# nrf52_pcb_layout.net
KiCad netlist of a schematic drawn in EAGLE
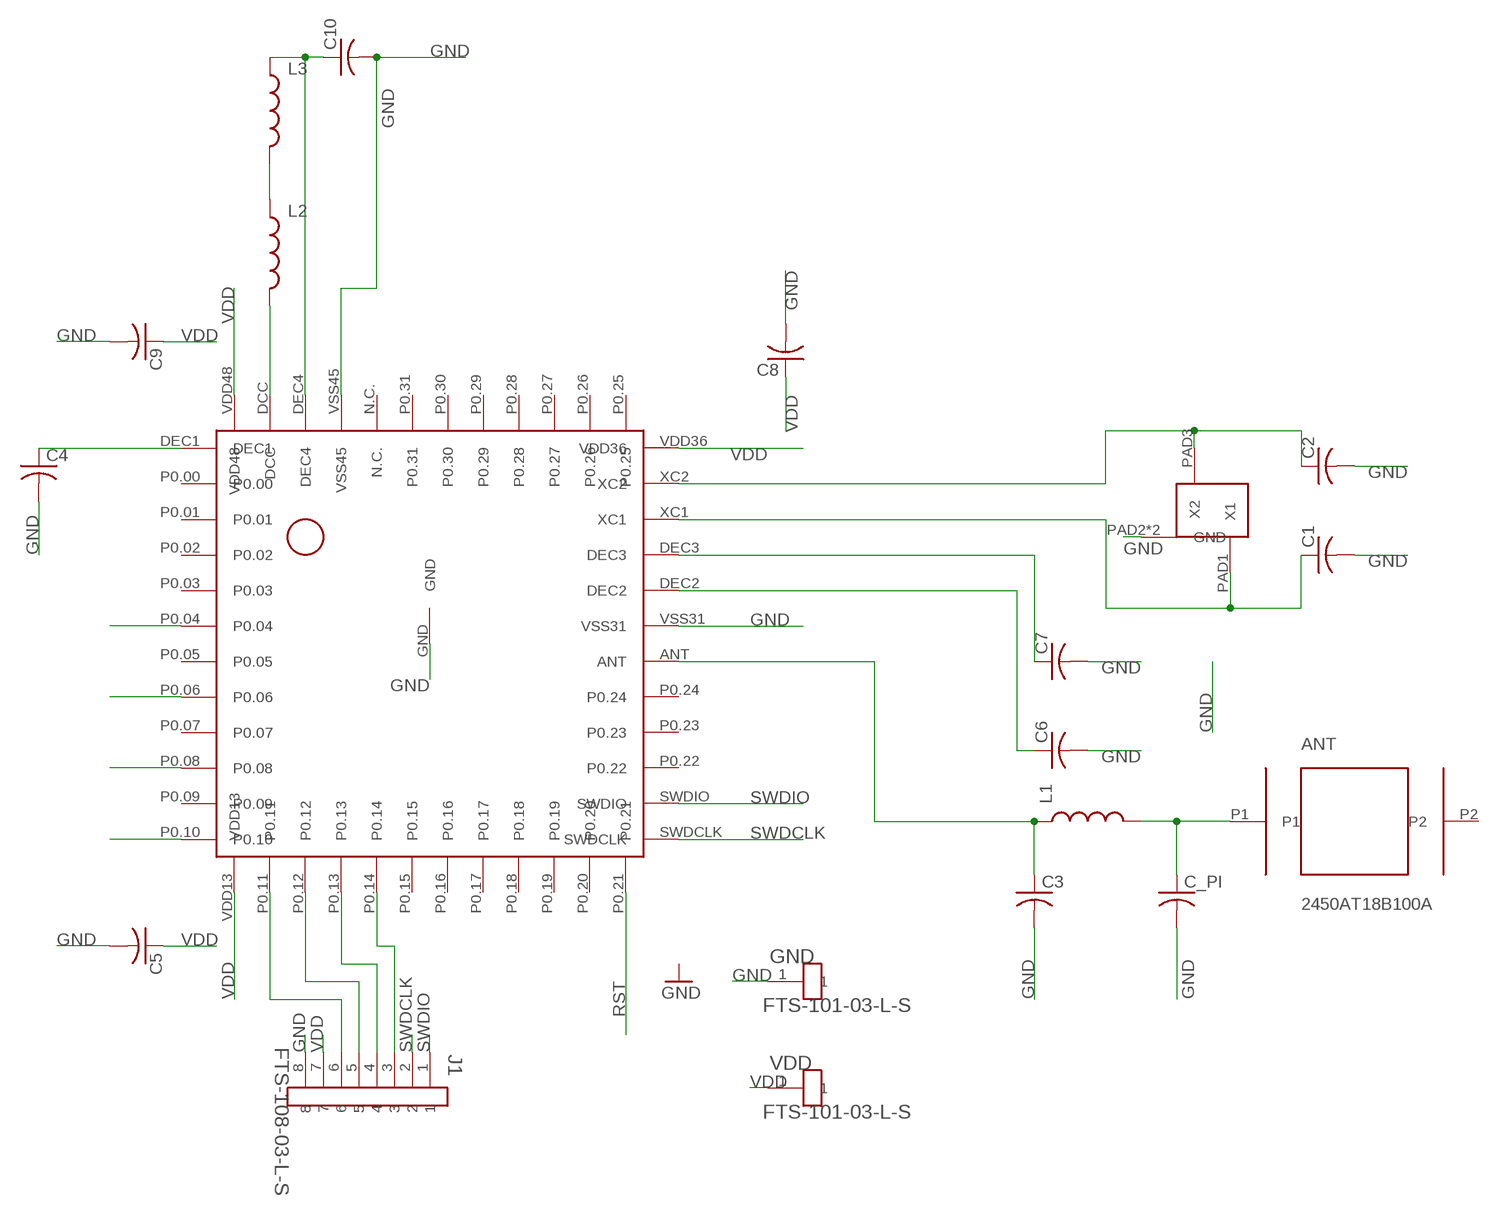
[diagram p0: schematic, sheet 1]

(export (version "E")
  (design (tool "Eeschema 10.0.6"))
  (components
    (comp (ref "ANT")
      (value "2450AT18B100A")
      (footprint "eagle-import:2450AT18B100")
      (libsource (lib "eagle-import") (part "2450AT18B100A"))
    )
    (comp (ref "C1")
      (value "C-USC0402")
      (footprint "eagle-import:C0402")
      (libsource (lib "eagle-import") (part "C-USC0402"))
    )
    (comp (ref "C2")
      (value "C-USC0402")
      (footprint "eagle-import:C0402")
      (libsource (lib "eagle-import") (part "C-USC0402"))
    )
    (comp (ref "C3")
      (value "C-USC0402")
      (footprint "eagle-import:C0402")
      (libsource (lib "eagle-import") (part "C-USC0402"))
    )
    (comp (ref "C4")
      (value "C-USC0402")
      (footprint "eagle-import:C0402")
      (libsource (lib "eagle-import") (part "C-USC0402"))
    )
    (comp (ref "C5")
      (value "C-USC0402")
      (footprint "eagle-import:C0402")
      (libsource (lib "eagle-import") (part "C-USC0402"))
    )
    (comp (ref "C6")
      (value "C-USC0402")
      (footprint "eagle-import:C0402")
      (libsource (lib "eagle-import") (part "C-USC0402"))
    )
    (comp (ref "C7")
      (value "C-USC0402")
      (footprint "eagle-import:C0402")
      (libsource (lib "eagle-import") (part "C-USC0402"))
    )
    (comp (ref "C8")
      (value "C-USC0402")
      (footprint "eagle-import:C0402")
      (libsource (lib "eagle-import") (part "C-USC0402"))
    )
    (comp (ref "C9")
      (value "C-USC0603")
      (footprint "eagle-import:C0603")
      (libsource (lib "eagle-import") (part "C-USC0603"))
    )
    (comp (ref "C10")
      (value "C-USC0603")
      (footprint "eagle-import:C0603")
      (libsource (lib "eagle-import") (part "C-USC0603"))
    )
    (comp (ref "C_PI")
      (value "C-USC0402")
      (footprint "eagle-import:C0402")
      (libsource (lib "eagle-import") (part "C-USC0402"))
    )
    (comp (ref "GND")
      (value "FTS-101-03-L-S")
      (footprint "eagle-import:SAMTEC_FTS-101-03-S")
      (libsource (lib "eagle-import") (part "FTS-101-03-L-S"))
    )
    (comp (ref "J1")
      (value "FTS-108-03-L-S")
      (footprint "eagle-import:SAMTEC_FTS-108-03-S")
      (fields (field (name "MPN") "FTS-108-03-L-D"))
      (libsource (lib "eagle-import") (part "FTS-108-03-L-S"))
    )
    (comp (ref "L1")
      (value "INDUCTOR0402")
      (footprint "eagle-import:C0402")
      (libsource (lib "eagle-import") (part "INDUCTOR0402"))
    )
    (comp (ref "L2")
      (value "INDUCTOR0603")
      (footprint "eagle-import:0603")
      (libsource (lib "eagle-import") (part "INDUCTOR0603"))
    )
    (comp (ref "L3")
      (value "INDUCTOR0402")
      (footprint "eagle-import:C0402")
      (libsource (lib "eagle-import") (part "INDUCTOR0402"))
    )
    (comp (ref "NRF52")
      (value "NRF52832-QFN48")
      (footprint "eagle-import:NRF52832-QFN48")
      (libsource (lib "eagle-import") (part "NRF52832-QFN48"))
    )
    (comp (ref "U$1")
      (value "EPSON-FA-128-32MHZ")
      (footprint "eagle-import:EPSON-FA-128-32MHZ")
      (libsource (lib "eagle-import") (part "EPSON-FA-128-32MHZ"))
    )
    (comp (ref "VDD")
      (value "FTS-101-03-L-S")
      (footprint "eagle-import:SAMTEC_FTS-101-03-S")
      (libsource (lib "eagle-import") (part "FTS-101-03-L-S"))
    )
  )
  (nets
    (net (code "1") (name "/RST") (class "Default")
      (node (ref "NRF52") (pin "P0.21") (pinfunction "P0.21_P0.21") (pintype "bidirectional"))
    )
    (net (code "2") (name "/SWDCLK") (class "Default")
      (node (ref "J1") (pin "2") (pinfunction "2_2") (pintype "passive"))
      (node (ref "NRF52") (pin "SWDCLK") (pinfunction "SWDCLK_SWDCLK") (pintype "bidirectional"))
    )
    (net (code "3") (name "/SWDIO") (class "Default")
      (node (ref "J1") (pin "1") (pinfunction "1_1") (pintype "passive"))
      (node (ref "NRF52") (pin "SWDIO") (pinfunction "SWDIO_SWDIO") (pintype "bidirectional"))
    )
    (net (code "4") (name "/VDD") (class "Default")
      (node (ref "C5") (pin "1") (pinfunction "1_1") (pintype "passive"))
      (node (ref "C8") (pin "1") (pinfunction "1_1") (pintype "passive"))
      (node (ref "C9") (pin "1") (pinfunction "1_1") (pintype "passive"))
      (node (ref "J1") (pin "7") (pinfunction "7_7") (pintype "passive"))
      (node (ref "NRF52") (pin "VDD13") (pinfunction "VDD13_VDD13") (pintype "bidirectional"))
      (node (ref "NRF52") (pin "VDD36") (pinfunction "VDD36_VDD36") (pintype "bidirectional"))
      (node (ref "NRF52") (pin "VDD48") (pinfunction "VDD48_VDD48") (pintype "bidirectional"))
      (node (ref "VDD") (pin "1") (pinfunction "1_1") (pintype "passive"))
    )
    (net (code "5") (name "GND") (class "Default")
      (node (ref "C1") (pin "2") (pinfunction "2_2") (pintype "passive"))
      (node (ref "C10") (pin "2") (pinfunction "2_2") (pintype "passive"))
      (node (ref "C2") (pin "2") (pinfunction "2_2") (pintype "passive"))
      (node (ref "C3") (pin "2") (pinfunction "2_2") (pintype "passive"))
      (node (ref "C4") (pin "2") (pinfunction "2_2") (pintype "passive"))
      (node (ref "C5") (pin "2") (pinfunction "2_2") (pintype "passive"))
      (node (ref "C6") (pin "2") (pinfunction "2_2") (pintype "passive"))
      (node (ref "C7") (pin "2") (pinfunction "2_2") (pintype "passive"))
      (node (ref "C8") (pin "2") (pinfunction "2_2") (pintype "passive"))
      (node (ref "C9") (pin "2") (pinfunction "2_2") (pintype "passive"))
      (node (ref "C_PI") (pin "2") (pinfunction "2_2") (pintype "passive"))
      (node (ref "GND") (pin "1") (pinfunction "1_1") (pintype "passive"))
      (node (ref "J1") (pin "8") (pinfunction "8_8") (pintype "passive"))
      (node (ref "NRF52") (pin "GND") (pinfunction "GND_GND") (pintype "bidirectional"))
      (node (ref "NRF52") (pin "VSS31") (pinfunction "VSS31_VSS31") (pintype "bidirectional"))
      (node (ref "NRF52") (pin "VSS45") (pinfunction "VSS45_VSS45") (pintype "bidirectional"))
      (node (ref "U$1") (pin "PAD2") (pinfunction "GND_PAD2") (pintype "bidirectional"))
      (node (ref "U$1") (pin "PAD4") (pinfunction "GND_PAD4") (pintype "bidirectional"))
    )
    (net (code "6") (name "Net-(ANT-PadP1)") (class "Default")
      (node (ref "ANT") (pin "P1") (pinfunction "P1_P1") (pintype "bidirectional"))
      (node (ref "C_PI") (pin "1") (pinfunction "1_1") (pintype "passive"))
      (node (ref "L1") (pin "2") (pinfunction "2_2") (pintype "passive"))
    )
    (net (code "7") (name "Net-(C3-Pad1)") (class "Default")
      (node (ref "C3") (pin "1") (pinfunction "1_1") (pintype "passive"))
      (node (ref "L1") (pin "1") (pinfunction "1_1") (pintype "passive"))
      (node (ref "NRF52") (pin "ANT") (pinfunction "ANT_ANT") (pintype "bidirectional"))
    )
    (net (code "8") (name "Net-(C4-Pad1)") (class "Default")
      (node (ref "C4") (pin "1") (pinfunction "1_1") (pintype "passive"))
      (node (ref "NRF52") (pin "DEC1") (pinfunction "DEC1_DEC1") (pintype "bidirectional"))
    )
    (net (code "9") (name "Net-(C6-Pad1)") (class "Default")
      (node (ref "C6") (pin "1") (pinfunction "1_1") (pintype "passive"))
      (node (ref "NRF52") (pin "DEC2") (pinfunction "DEC2_DEC2") (pintype "bidirectional"))
    )
    (net (code "10") (name "Net-(C7-Pad1)") (class "Default")
      (node (ref "C7") (pin "1") (pinfunction "1_1") (pintype "passive"))
      (node (ref "NRF52") (pin "DEC3") (pinfunction "DEC3_DEC3") (pintype "bidirectional"))
    )
    (net (code "11") (name "Net-(C10-Pad1)") (class "Default")
      (node (ref "C10") (pin "1") (pinfunction "1_1") (pintype "passive"))
      (node (ref "L3") (pin "1") (pinfunction "1_1") (pintype "passive"))
      (node (ref "NRF52") (pin "DEC4") (pinfunction "DEC4_DEC4") (pintype "bidirectional"))
    )
    (net (code "12") (name "Net-(J1-Pad3)") (class "Default")
      (node (ref "J1") (pin "3") (pinfunction "3_3") (pintype "passive"))
      (node (ref "NRF52") (pin "P0.14") (pinfunction "P0.14_P0.14") (pintype "bidirectional"))
    )
    (net (code "13") (name "Net-(J1-Pad4)") (class "Default")
      (node (ref "J1") (pin "4") (pinfunction "4_4") (pintype "passive"))
      (node (ref "NRF52") (pin "P0.13") (pinfunction "P0.13_P0.13") (pintype "bidirectional"))
    )
    (net (code "14") (name "Net-(J1-Pad5)") (class "Default")
      (node (ref "J1") (pin "5") (pinfunction "5_5") (pintype "passive"))
      (node (ref "NRF52") (pin "P0.12") (pinfunction "P0.12_P0.12") (pintype "bidirectional"))
    )
    (net (code "15") (name "Net-(J1-Pad6)") (class "Default")
      (node (ref "J1") (pin "6") (pinfunction "6_6") (pintype "passive"))
      (node (ref "NRF52") (pin "P0.11") (pinfunction "P0.11_P0.11") (pintype "bidirectional"))
    )
    (net (code "16") (name "Net-(L2-Pad1)") (class "Default")
      (node (ref "L2") (pin "1") (pinfunction "1_1") (pintype "passive"))
      (node (ref "L3") (pin "2") (pinfunction "2_2") (pintype "passive"))
    )
    (net (code "17") (name "Net-(L2-Pad2)") (class "Default")
      (node (ref "L2") (pin "2") (pinfunction "2_2") (pintype "passive"))
      (node (ref "NRF52") (pin "DCC") (pinfunction "DCC_DCC") (pintype "bidirectional"))
    )
    (net (code "18") (name "Net-(U$1-X1)") (class "Default")
      (node (ref "C1") (pin "1") (pinfunction "1_1") (pintype "passive"))
      (node (ref "NRF52") (pin "XC1") (pinfunction "XC1_XC1") (pintype "bidirectional"))
      (node (ref "U$1") (pin "PAD1") (pinfunction "X1_PAD1") (pintype "bidirectional"))
    )
    (net (code "19") (name "Net-(U$1-X2)") (class "Default")
      (node (ref "C2") (pin "1") (pinfunction "1_1") (pintype "passive"))
      (node (ref "NRF52") (pin "XC2") (pinfunction "XC2_XC2") (pintype "bidirectional"))
      (node (ref "U$1") (pin "PAD3") (pinfunction "X2_PAD3") (pintype "bidirectional"))
    )
    (net (code "20") (name "unconnected-(ANT-PadP2)") (class "Default")
      (node (ref "ANT") (pin "P2") (pinfunction "P2_P2") (pintype "bidirectional"))
    )
    (net (code "21") (name "unconnected-(NRF52-PadN.C.)") (class "Default")
      (node (ref "NRF52") (pin "N.C.") (pinfunction "N.C._N.C.") (pintype "bidirectional"))
    )
    (net (code "22") (name "unconnected-(NRF52-PadP0.00)") (class "Default")
      (node (ref "NRF52") (pin "P0.00") (pinfunction "P0.00_P0.00") (pintype "bidirectional"))
    )
    (net (code "23") (name "unconnected-(NRF52-PadP0.01)") (class "Default")
      (node (ref "NRF52") (pin "P0.01") (pinfunction "P0.01_P0.01") (pintype "bidirectional"))
    )
    (net (code "24") (name "unconnected-(NRF52-PadP0.02)") (class "Default")
      (node (ref "NRF52") (pin "P0.02") (pinfunction "P0.02_P0.02") (pintype "bidirectional"))
    )
    (net (code "25") (name "unconnected-(NRF52-PadP0.03)") (class "Default")
      (node (ref "NRF52") (pin "P0.03") (pinfunction "P0.03_P0.03") (pintype "bidirectional"))
    )
    (net (code "26") (name "unconnected-(NRF52-PadP0.04)") (class "Default")
      (node (ref "NRF52") (pin "P0.04") (pinfunction "P0.04_P0.04") (pintype "bidirectional"))
    )
    (net (code "27") (name "unconnected-(NRF52-PadP0.05)") (class "Default")
      (node (ref "NRF52") (pin "P0.05") (pinfunction "P0.05_P0.05") (pintype "bidirectional"))
    )
    (net (code "28") (name "unconnected-(NRF52-PadP0.06)") (class "Default")
      (node (ref "NRF52") (pin "P0.06") (pinfunction "P0.06_P0.06") (pintype "bidirectional"))
    )
    (net (code "29") (name "unconnected-(NRF52-PadP0.07)") (class "Default")
      (node (ref "NRF52") (pin "P0.07") (pinfunction "P0.07_P0.07") (pintype "bidirectional"))
    )
    (net (code "30") (name "unconnected-(NRF52-PadP0.08)") (class "Default")
      (node (ref "NRF52") (pin "P0.08") (pinfunction "P0.08_P0.08") (pintype "bidirectional"))
    )
    (net (code "31") (name "unconnected-(NRF52-PadP0.09)") (class "Default")
      (node (ref "NRF52") (pin "P0.09") (pinfunction "P0.09_P0.09") (pintype "bidirectional"))
    )
    (net (code "32") (name "unconnected-(NRF52-PadP0.10)") (class "Default")
      (node (ref "NRF52") (pin "P0.10") (pinfunction "P0.10_P0.10") (pintype "bidirectional"))
    )
    (net (code "33") (name "unconnected-(NRF52-PadP0.15)") (class "Default")
      (node (ref "NRF52") (pin "P0.15") (pinfunction "P0.15_P0.15") (pintype "bidirectional"))
    )
    (net (code "34") (name "unconnected-(NRF52-PadP0.16)") (class "Default")
      (node (ref "NRF52") (pin "P0.16") (pinfunction "P0.16_P0.16") (pintype "bidirectional"))
    )
    (net (code "35") (name "unconnected-(NRF52-PadP0.17)") (class "Default")
      (node (ref "NRF52") (pin "P0.17") (pinfunction "P0.17_P0.17") (pintype "bidirectional"))
    )
    (net (code "36") (name "unconnected-(NRF52-PadP0.18)") (class "Default")
      (node (ref "NRF52") (pin "P0.18") (pinfunction "P0.18_P0.18") (pintype "bidirectional"))
    )
    (net (code "37") (name "unconnected-(NRF52-PadP0.19)") (class "Default")
      (node (ref "NRF52") (pin "P0.19") (pinfunction "P0.19_P0.19") (pintype "bidirectional"))
    )
    (net (code "38") (name "unconnected-(NRF52-PadP0.20)") (class "Default")
      (node (ref "NRF52") (pin "P0.20") (pinfunction "P0.20_P0.20") (pintype "bidirectional"))
    )
    (net (code "39") (name "unconnected-(NRF52-PadP0.22)") (class "Default")
      (node (ref "NRF52") (pin "P0.22") (pinfunction "P0.22_P0.22") (pintype "bidirectional"))
    )
    (net (code "40") (name "unconnected-(NRF52-PadP0.23)") (class "Default")
      (node (ref "NRF52") (pin "P0.23") (pinfunction "P0.23_P0.23") (pintype "bidirectional"))
    )
    (net (code "41") (name "unconnected-(NRF52-PadP0.24)") (class "Default")
      (node (ref "NRF52") (pin "P0.24") (pinfunction "P0.24_P0.24") (pintype "bidirectional"))
    )
    (net (code "42") (name "unconnected-(NRF52-PadP0.25)") (class "Default")
      (node (ref "NRF52") (pin "P0.25") (pinfunction "P0.25_P0.25") (pintype "bidirectional"))
    )
    (net (code "43") (name "unconnected-(NRF52-PadP0.26)") (class "Default")
      (node (ref "NRF52") (pin "P0.26") (pinfunction "P0.26_P0.26") (pintype "bidirectional"))
    )
    (net (code "44") (name "unconnected-(NRF52-PadP0.27)") (class "Default")
      (node (ref "NRF52") (pin "P0.27") (pinfunction "P0.27_P0.27") (pintype "bidirectional"))
    )
    (net (code "45") (name "unconnected-(NRF52-PadP0.28)") (class "Default")
      (node (ref "NRF52") (pin "P0.28") (pinfunction "P0.28_P0.28") (pintype "bidirectional"))
    )
    (net (code "46") (name "unconnected-(NRF52-PadP0.29)") (class "Default")
      (node (ref "NRF52") (pin "P0.29") (pinfunction "P0.29_P0.29") (pintype "bidirectional"))
    )
    (net (code "47") (name "unconnected-(NRF52-PadP0.30)") (class "Default")
      (node (ref "NRF52") (pin "P0.30") (pinfunction "P0.30_P0.30") (pintype "bidirectional"))
    )
    (net (code "48") (name "unconnected-(NRF52-PadP0.31)") (class "Default")
      (node (ref "NRF52") (pin "P0.31") (pinfunction "P0.31_P0.31") (pintype "bidirectional"))
    )
  )
)
